# OpenSegment-v11.net
KiCad netlist of a schematic drawn in EAGLE
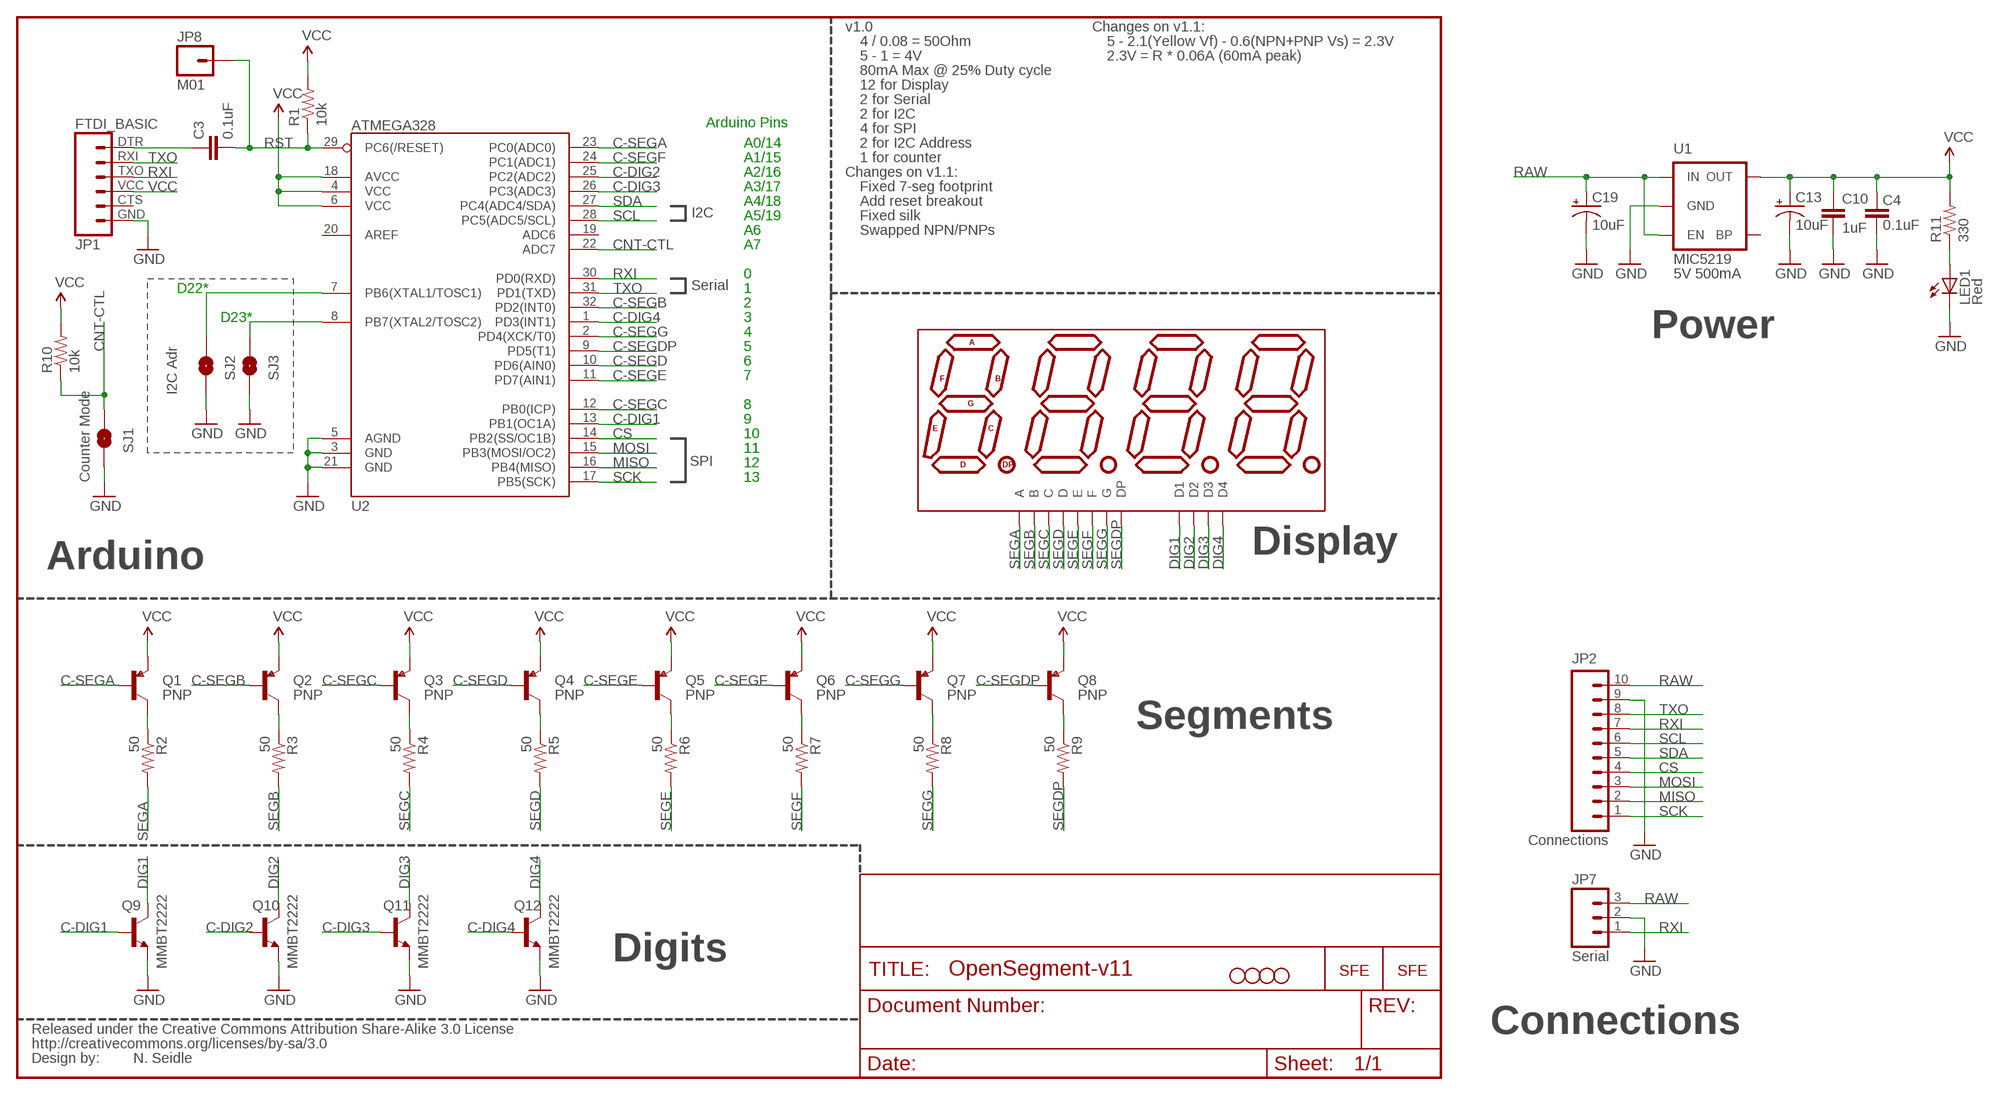
[diagram p0: schematic, sheet 1]

(export (version "E")
  (design (tool "Eeschema 10.0.6"))
  (components
    (comp (ref "C3")
      (value "0.1uF")
      (footprint "eagle-import:0402-CAP")
      (libsource (lib "eagle-import") (part "CAP0402-CAP"))
    )
    (comp (ref "C4")
      (value "0.1uF")
      (footprint "eagle-import:0402-CAP")
      (libsource (lib "eagle-import") (part "CAP0402-CAP"))
    )
    (comp (ref "C10")
      (value "1uF")
      (footprint "eagle-import:0402-CAP")
      (libsource (lib "eagle-import") (part "CAP0402-CAP"))
    )
    (comp (ref "C13")
      (value "10uF")
      (footprint "eagle-import:EIA3216")
      (libsource (lib "eagle-import") (part "CAP_POL1206"))
    )
    (comp (ref "C19")
      (value "10uF")
      (footprint "eagle-import:EIA3216")
      (libsource (lib "eagle-import") (part "CAP_POL1206"))
    )
    (comp (ref "JP1")
      (value "FTDI_BASIC")
      (footprint "eagle-import:FTDI_BASIC")
      (libsource (lib "eagle-import") (part "FTDI_BASICPTH"))
    )
    (comp (ref "JP2")
      (value "Connections")
      (footprint "eagle-import:1X10")
      (libsource (lib "eagle-import") (part "M10{dblquote}"))
    )
    (comp (ref "JP3")
      (value "STAND-OFF")
      (footprint "eagle-import:STAND-OFF")
      (libsource (lib "eagle-import") (part "STAND-OFF"))
    )
    (comp (ref "JP4")
      (value "STAND-OFF")
      (footprint "eagle-import:STAND-OFF")
      (libsource (lib "eagle-import") (part "STAND-OFF"))
    )
    (comp (ref "JP5")
      (value "STAND-OFF")
      (footprint "eagle-import:STAND-OFF")
      (libsource (lib "eagle-import") (part "STAND-OFF"))
    )
    (comp (ref "JP6")
      (value "STAND-OFF")
      (footprint "eagle-import:STAND-OFF")
      (libsource (lib "eagle-import") (part "STAND-OFF"))
    )
    (comp (ref "JP7")
      (value "Serial")
      (footprint "eagle-import:JST-3-SMD")
      (libsource (lib "eagle-import") (part "M03"))
    )
    (comp (ref "JP8")
      (value "M01")
      (footprint "eagle-import:1X01")
      (libsource (lib "eagle-import") (part "M01PTH"))
    )
    (comp (ref "LED1")
      (value "Red")
      (footprint "eagle-import:LED-0603")
      (libsource (lib "eagle-import") (part "LED0603"))
    )
    (comp (ref "Q1")
      (value "PNP")
      (footprint "eagle-import:SOT23-3")
      (libsource (lib "eagle-import") (part "TRANSISTOR_PNPSMD"))
    )
    (comp (ref "Q2")
      (value "PNP")
      (footprint "eagle-import:SOT23-3")
      (libsource (lib "eagle-import") (part "TRANSISTOR_PNPSMD"))
    )
    (comp (ref "Q3")
      (value "PNP")
      (footprint "eagle-import:SOT23-3")
      (libsource (lib "eagle-import") (part "TRANSISTOR_PNPSMD"))
    )
    (comp (ref "Q4")
      (value "PNP")
      (footprint "eagle-import:SOT23-3")
      (libsource (lib "eagle-import") (part "TRANSISTOR_PNPSMD"))
    )
    (comp (ref "Q5")
      (value "PNP")
      (footprint "eagle-import:SOT23-3")
      (libsource (lib "eagle-import") (part "TRANSISTOR_PNPSMD"))
    )
    (comp (ref "Q6")
      (value "PNP")
      (footprint "eagle-import:SOT23-3")
      (libsource (lib "eagle-import") (part "TRANSISTOR_PNPSMD"))
    )
    (comp (ref "Q7")
      (value "PNP")
      (footprint "eagle-import:SOT23-3")
      (libsource (lib "eagle-import") (part "TRANSISTOR_PNPSMD"))
    )
    (comp (ref "Q8")
      (value "PNP")
      (footprint "eagle-import:SOT23-3")
      (libsource (lib "eagle-import") (part "TRANSISTOR_PNPSMD"))
    )
    (comp (ref "Q9")
      (value "MMBT2222")
      (footprint "eagle-import:SOT23-3")
      (libsource (lib "eagle-import") (part "TRANSISTOR_NPNSOT23-3"))
    )
    (comp (ref "Q10")
      (value "MMBT2222")
      (footprint "eagle-import:SOT23-3")
      (libsource (lib "eagle-import") (part "TRANSISTOR_NPNSOT23-3"))
    )
    (comp (ref "Q11")
      (value "MMBT2222")
      (footprint "eagle-import:SOT23-3")
      (libsource (lib "eagle-import") (part "TRANSISTOR_NPNSOT23-3"))
    )
    (comp (ref "Q12")
      (value "MMBT2222")
      (footprint "eagle-import:SOT23-3")
      (libsource (lib "eagle-import") (part "TRANSISTOR_NPNSOT23-3"))
    )
    (comp (ref "R1")
      (value "10k")
      (footprint "eagle-import:0402-RES")
      (libsource (lib "eagle-import") (part "RESISTOR0402-RES"))
    )
    (comp (ref "R2")
      (value "50")
      (footprint "eagle-import:0402-RES")
      (libsource (lib "eagle-import") (part "RESISTOR0402-RES"))
    )
    (comp (ref "R3")
      (value "50")
      (footprint "eagle-import:0402-RES")
      (libsource (lib "eagle-import") (part "RESISTOR0402-RES"))
    )
    (comp (ref "R4")
      (value "50")
      (footprint "eagle-import:0402-RES")
      (libsource (lib "eagle-import") (part "RESISTOR0402-RES"))
    )
    (comp (ref "R5")
      (value "50")
      (footprint "eagle-import:0402-RES")
      (libsource (lib "eagle-import") (part "RESISTOR0402-RES"))
    )
    (comp (ref "R6")
      (value "50")
      (footprint "eagle-import:0402-RES")
      (libsource (lib "eagle-import") (part "RESISTOR0402-RES"))
    )
    (comp (ref "R7")
      (value "50")
      (footprint "eagle-import:0402-RES")
      (libsource (lib "eagle-import") (part "RESISTOR0402-RES"))
    )
    (comp (ref "R8")
      (value "50")
      (footprint "eagle-import:0402-RES")
      (libsource (lib "eagle-import") (part "RESISTOR0402-RES"))
    )
    (comp (ref "R9")
      (value "50")
      (footprint "eagle-import:0402-RES")
      (libsource (lib "eagle-import") (part "RESISTOR0402-RES"))
    )
    (comp (ref "R10")
      (value "10k")
      (footprint "eagle-import:0402-RES")
      (libsource (lib "eagle-import") (part "RESISTOR0402-RES"))
    )
    (comp (ref "R11")
      (value "330")
      (footprint "eagle-import:0402-RES")
      (libsource (lib "eagle-import") (part "RESISTOR0402-RES"))
    )
    (comp (ref "SJ1")
      (value "Counter Ctl")
      (footprint "eagle-import:SJ_2S-NO")
      (libsource (lib "eagle-import") (part "SOLDERJUMPERNO"))
    )
    (comp (ref "SJ2")
      (value "Counter Ctl")
      (footprint "eagle-import:SJ_2S-NO")
      (libsource (lib "eagle-import") (part "SOLDERJUMPERNO"))
    )
    (comp (ref "SJ3")
      (value "Counter Ctl")
      (footprint "eagle-import:SJ_2S-NO")
      (libsource (lib "eagle-import") (part "SOLDERJUMPERNO"))
    )
    (comp (ref "U$2")
      (value "LOGO-SFESK")
      (footprint "eagle-import:SFE-LOGO-FLAME")
      (libsource (lib "eagle-import") (part "LOGO-SFESK"))
    )
    (comp (ref "U$3")
      (value "CREATIVE_COMMONS")
      (footprint "eagle-import:CREATIVE_COMMONS")
      (libsource (lib "eagle-import") (part "CREATIVE_COMMONS"))
    )
    (comp (ref "U$7")
      (value "LOGO-SFENW2")
      (footprint "eagle-import:SFE-NEW-WEB")
      (libsource (lib "eagle-import") (part "LOGO-SFENW2"))
    )
    (comp (ref "U1")
      (value "MIC5219")
      (footprint "eagle-import:SOT23-5")
      (libsource (lib "eagle-import") (part "V_REG_LDOSMD"))
    )
    (comp (ref "U2")
      (value "ATMEGA328")
      (footprint "eagle-import:TQFP32-08")
      (libsource (lib "eagle-import") (part "ATMEGA168"))
    )
    (comp (ref "U3")
      (value "7-SEGMENT-4DIGIT-COUNTERPTH")
      (footprint "eagle-import:7-SEGMENT-4DIGIT-COUNTER")
      (libsource (lib "eagle-import") (part "7-SEGMENT-4DIGIT-COUNTERPTH"))
    )
  )
  (nets
    (net (code "1") (name "/C-DIG1") (class "Default")
      (node (ref "Q9") (pin "1") (pinfunction "B_1") (pintype "passive"))
      (node (ref "U2") (pin "13") (pinfunction "PB1(OC1A)_13") (pintype "bidirectional"))
    )
    (net (code "2") (name "/C-DIG2") (class "Default")
      (node (ref "Q10") (pin "1") (pinfunction "B_1") (pintype "passive"))
      (node (ref "U2") (pin "25") (pinfunction "PC2(ADC2)_25") (pintype "bidirectional"))
    )
    (net (code "3") (name "/C-DIG3") (class "Default")
      (node (ref "Q11") (pin "1") (pinfunction "B_1") (pintype "passive"))
      (node (ref "U2") (pin "26") (pinfunction "PC3(ADC3)_26") (pintype "bidirectional"))
    )
    (net (code "4") (name "/C-DIG4") (class "Default")
      (node (ref "Q12") (pin "1") (pinfunction "B_1") (pintype "passive"))
      (node (ref "U2") (pin "1") (pinfunction "PD3(INT1)_1") (pintype "bidirectional"))
    )
    (net (code "5") (name "/C-SEGA") (class "Default")
      (node (ref "Q1") (pin "1") (pinfunction "B_1") (pintype "passive"))
      (node (ref "U2") (pin "23") (pinfunction "PC0(ADC0)_23") (pintype "bidirectional"))
    )
    (net (code "6") (name "/C-SEGB") (class "Default")
      (node (ref "Q2") (pin "1") (pinfunction "B_1") (pintype "passive"))
      (node (ref "U2") (pin "32") (pinfunction "PD2(INT0)_32") (pintype "bidirectional"))
    )
    (net (code "7") (name "/C-SEGC") (class "Default")
      (node (ref "Q3") (pin "1") (pinfunction "B_1") (pintype "passive"))
      (node (ref "U2") (pin "12") (pinfunction "PB0(ICP)_12") (pintype "bidirectional"))
    )
    (net (code "8") (name "/C-SEGD") (class "Default")
      (node (ref "Q4") (pin "1") (pinfunction "B_1") (pintype "passive"))
      (node (ref "U2") (pin "10") (pinfunction "PD6(AIN0)_10") (pintype "bidirectional"))
    )
    (net (code "9") (name "/C-SEGDP") (class "Default")
      (node (ref "Q8") (pin "1") (pinfunction "B_1") (pintype "passive"))
      (node (ref "U2") (pin "9") (pinfunction "PD5(T1)_9") (pintype "bidirectional"))
    )
    (net (code "10") (name "/C-SEGE") (class "Default")
      (node (ref "Q5") (pin "1") (pinfunction "B_1") (pintype "passive"))
      (node (ref "U2") (pin "11") (pinfunction "PD7(AIN1)_11") (pintype "bidirectional"))
    )
    (net (code "11") (name "/C-SEGF") (class "Default")
      (node (ref "Q6") (pin "1") (pinfunction "B_1") (pintype "passive"))
      (node (ref "U2") (pin "24") (pinfunction "PC1(ADC1)_24") (pintype "bidirectional"))
    )
    (net (code "12") (name "/C-SEGG") (class "Default")
      (node (ref "Q7") (pin "1") (pinfunction "B_1") (pintype "passive"))
      (node (ref "U2") (pin "2") (pinfunction "PD4(XCK/T0)_2") (pintype "bidirectional"))
    )
    (net (code "13") (name "/CNT-CTL") (class "Default")
      (node (ref "R10") (pin "1") (pinfunction "1_1") (pintype "passive"))
      (node (ref "SJ1") (pin "1") (pinfunction "1_1") (pintype "passive"))
      (node (ref "U2") (pin "22") (pinfunction "ADC7_22") (pintype "bidirectional"))
    )
    (net (code "14") (name "/CS") (class "Default")
      (node (ref "JP2") (pin "4") (pinfunction "4_4") (pintype "passive"))
      (node (ref "U2") (pin "14") (pinfunction "PB2(SS/OC1B)_14") (pintype "bidirectional"))
    )
    (net (code "15") (name "/DIG1") (class "Default")
      (node (ref "Q9") (pin "3") (pinfunction "C_3") (pintype "passive"))
      (node (ref "U3") (pin "12") (pinfunction "D1_12") (pintype "bidirectional"))
    )
    (net (code "16") (name "/DIG2") (class "Default")
      (node (ref "Q10") (pin "3") (pinfunction "C_3") (pintype "passive"))
      (node (ref "U3") (pin "9") (pinfunction "D2_9") (pintype "bidirectional"))
    )
    (net (code "17") (name "/DIG3") (class "Default")
      (node (ref "Q11") (pin "3") (pinfunction "C_3") (pintype "passive"))
      (node (ref "U3") (pin "8") (pinfunction "D3_8") (pintype "bidirectional"))
    )
    (net (code "18") (name "/DIG4") (class "Default")
      (node (ref "Q12") (pin "3") (pinfunction "C_3") (pintype "passive"))
      (node (ref "U3") (pin "6") (pinfunction "D4_6") (pintype "bidirectional"))
    )
    (net (code "19") (name "/MISO") (class "Default")
      (node (ref "JP2") (pin "2") (pinfunction "2_2") (pintype "passive"))
      (node (ref "U2") (pin "16") (pinfunction "PB4(MISO)_16") (pintype "bidirectional"))
    )
    (net (code "20") (name "/MOSI") (class "Default")
      (node (ref "JP2") (pin "3") (pinfunction "3_3") (pintype "passive"))
      (node (ref "U2") (pin "15") (pinfunction "PB3(MOSI/OC2)_15") (pintype "bidirectional"))
    )
    (net (code "21") (name "/RAW") (class "Default")
      (node (ref "C19") (pin "A") (pinfunction "+_A") (pintype "passive"))
      (node (ref "JP2") (pin "10") (pinfunction "10_10") (pintype "passive"))
      (node (ref "JP7") (pin "3") (pinfunction "3_3") (pintype "passive"))
      (node (ref "U1") (pin "1") (pinfunction "IN_1") (pintype "input"))
      (node (ref "U1") (pin "3") (pinfunction "EN_3") (pintype "input"))
    )
    (net (code "22") (name "/RST") (class "Default")
      (node (ref "C3") (pin "2") (pinfunction "2_2") (pintype "passive"))
      (node (ref "JP8") (pin "1") (pinfunction "1_1") (pintype "passive"))
      (node (ref "R1") (pin "1") (pinfunction "1_1") (pintype "passive"))
      (node (ref "U2") (pin "29") (pinfunction "PC6(/RESET)_29") (pintype "bidirectional"))
    )
    (net (code "23") (name "/RXI") (class "Default")
      (node (ref "JP1") (pin "TXO") (pinfunction "3_TXO") (pintype "passive"))
      (node (ref "JP2") (pin "7") (pinfunction "7_7") (pintype "passive"))
      (node (ref "JP7") (pin "1") (pinfunction "1_1") (pintype "passive"))
      (node (ref "U2") (pin "30") (pinfunction "PD0(RXD)_30") (pintype "bidirectional"))
    )
    (net (code "24") (name "/SCK") (class "Default")
      (node (ref "JP2") (pin "1") (pinfunction "1_1") (pintype "passive"))
      (node (ref "U2") (pin "17") (pinfunction "PB5(SCK)_17") (pintype "bidirectional"))
    )
    (net (code "25") (name "/SCL") (class "Default")
      (node (ref "JP2") (pin "6") (pinfunction "6_6") (pintype "passive"))
      (node (ref "U2") (pin "28") (pinfunction "PC5(ADC5/SCL)_28") (pintype "bidirectional"))
    )
    (net (code "26") (name "/SDA") (class "Default")
      (node (ref "JP2") (pin "5") (pinfunction "5_5") (pintype "passive"))
      (node (ref "U2") (pin "27") (pinfunction "PC4(ADC4/SDA)_27") (pintype "bidirectional"))
    )
    (net (code "27") (name "/SEGA") (class "Default")
      (node (ref "R2") (pin "2") (pinfunction "2_2") (pintype "passive"))
      (node (ref "U3") (pin "11") (pinfunction "A_11") (pintype "bidirectional"))
    )
    (net (code "28") (name "/SEGB") (class "Default")
      (node (ref "R3") (pin "2") (pinfunction "2_2") (pintype "passive"))
      (node (ref "U3") (pin "7") (pinfunction "B_7") (pintype "bidirectional"))
    )
    (net (code "29") (name "/SEGC") (class "Default")
      (node (ref "R4") (pin "2") (pinfunction "2_2") (pintype "passive"))
      (node (ref "U3") (pin "4") (pinfunction "C_4") (pintype "bidirectional"))
    )
    (net (code "30") (name "/SEGD") (class "Default")
      (node (ref "R5") (pin "2") (pinfunction "2_2") (pintype "passive"))
      (node (ref "U3") (pin "2") (pinfunction "D_2") (pintype "bidirectional"))
    )
    (net (code "31") (name "/SEGDP") (class "Default")
      (node (ref "R9") (pin "2") (pinfunction "2_2") (pintype "passive"))
      (node (ref "U3") (pin "3") (pinfunction "DP_3") (pintype "bidirectional"))
    )
    (net (code "32") (name "/SEGE") (class "Default")
      (node (ref "R6") (pin "2") (pinfunction "2_2") (pintype "passive"))
      (node (ref "U3") (pin "1") (pinfunction "E_1") (pintype "bidirectional"))
    )
    (net (code "33") (name "/SEGF") (class "Default")
      (node (ref "R7") (pin "2") (pinfunction "2_2") (pintype "passive"))
      (node (ref "U3") (pin "10") (pinfunction "F_10") (pintype "bidirectional"))
    )
    (net (code "34") (name "/SEGG") (class "Default")
      (node (ref "R8") (pin "2") (pinfunction "2_2") (pintype "passive"))
      (node (ref "U3") (pin "5") (pinfunction "G_5") (pintype "bidirectional"))
    )
    (net (code "35") (name "/TXO") (class "Default")
      (node (ref "JP1") (pin "RXI") (pinfunction "2_RXI") (pintype "passive"))
      (node (ref "JP2") (pin "8") (pinfunction "8_8") (pintype "passive"))
      (node (ref "U2") (pin "31") (pinfunction "PD1(TXD)_31") (pintype "bidirectional"))
    )
    (net (code "36") (name "GND") (class "Default")
      (node (ref "C10") (pin "2") (pinfunction "2_2") (pintype "passive"))
      (node (ref "C13") (pin "C") (pinfunction "-_C") (pintype "passive"))
      (node (ref "C19") (pin "C") (pinfunction "-_C") (pintype "passive"))
      (node (ref "C4") (pin "1") (pinfunction "1_1") (pintype "passive"))
      (node (ref "JP1") (pin "GND") (pinfunction "6_GND") (pintype "passive"))
      (node (ref "JP2") (pin "9") (pinfunction "9_9") (pintype "passive"))
      (node (ref "JP7") (pin "2") (pinfunction "2_2") (pintype "passive"))
      (node (ref "LED1") (pin "C") (pinfunction "C_C") (pintype "passive"))
      (node (ref "Q10") (pin "2") (pinfunction "E_2") (pintype "passive"))
      (node (ref "Q11") (pin "2") (pinfunction "E_2") (pintype "passive"))
      (node (ref "Q12") (pin "2") (pinfunction "E_2") (pintype "passive"))
      (node (ref "Q9") (pin "2") (pinfunction "E_2") (pintype "passive"))
      (node (ref "SJ1") (pin "2") (pinfunction "2_2") (pintype "passive"))
      (node (ref "SJ2") (pin "2") (pinfunction "2_2") (pintype "passive"))
      (node (ref "SJ3") (pin "2") (pinfunction "2_2") (pintype "passive"))
      (node (ref "U1") (pin "2") (pinfunction "GND_2") (pintype "input"))
      (node (ref "U2") (pin "21") (pinfunction "GND_21") (pintype "bidirectional"))
      (node (ref "U2") (pin "3") (pinfunction "GND_3") (pintype "bidirectional"))
      (node (ref "U2") (pin "5") (pinfunction "AGND_5") (pintype "bidirectional"))
    )
    (net (code "37") (name "Net-(JP1-1)") (class "Default")
      (node (ref "C3") (pin "1") (pinfunction "1_1") (pintype "passive"))
      (node (ref "JP1") (pin "DTR") (pinfunction "1_DTR") (pintype "passive"))
    )
    (net (code "38") (name "Net-(LED1-PadA)") (class "Default")
      (node (ref "LED1") (pin "A") (pinfunction "A_A") (pintype "passive"))
      (node (ref "R11") (pin "1") (pinfunction "1_1") (pintype "passive"))
    )
    (net (code "39") (name "Net-(Q1-C)") (class "Default")
      (node (ref "Q1") (pin "3") (pinfunction "C_3") (pintype "passive"))
      (node (ref "R2") (pin "1") (pinfunction "1_1") (pintype "passive"))
    )
    (net (code "40") (name "Net-(Q2-C)") (class "Default")
      (node (ref "Q2") (pin "3") (pinfunction "C_3") (pintype "passive"))
      (node (ref "R3") (pin "1") (pinfunction "1_1") (pintype "passive"))
    )
    (net (code "41") (name "Net-(Q3-C)") (class "Default")
      (node (ref "Q3") (pin "3") (pinfunction "C_3") (pintype "passive"))
      (node (ref "R4") (pin "1") (pinfunction "1_1") (pintype "passive"))
    )
    (net (code "42") (name "Net-(Q4-C)") (class "Default")
      (node (ref "Q4") (pin "3") (pinfunction "C_3") (pintype "passive"))
      (node (ref "R5") (pin "1") (pinfunction "1_1") (pintype "passive"))
    )
    (net (code "43") (name "Net-(Q5-C)") (class "Default")
      (node (ref "Q5") (pin "3") (pinfunction "C_3") (pintype "passive"))
      (node (ref "R6") (pin "1") (pinfunction "1_1") (pintype "passive"))
    )
    (net (code "44") (name "Net-(Q6-C)") (class "Default")
      (node (ref "Q6") (pin "3") (pinfunction "C_3") (pintype "passive"))
      (node (ref "R7") (pin "1") (pinfunction "1_1") (pintype "passive"))
    )
    (net (code "45") (name "Net-(Q7-C)") (class "Default")
      (node (ref "Q7") (pin "3") (pinfunction "C_3") (pintype "passive"))
      (node (ref "R8") (pin "1") (pinfunction "1_1") (pintype "passive"))
    )
    (net (code "46") (name "Net-(Q8-C)") (class "Default")
      (node (ref "Q8") (pin "3") (pinfunction "C_3") (pintype "passive"))
      (node (ref "R9") (pin "1") (pinfunction "1_1") (pintype "passive"))
    )
    (net (code "47") (name "Net-(U2-PB6(XTAL1{slash}TOSC1))") (class "Default")
      (node (ref "SJ2") (pin "1") (pinfunction "1_1") (pintype "passive"))
      (node (ref "U2") (pin "7") (pinfunction "PB6(XTAL1/TOSC1)_7") (pintype "bidirectional"))
    )
    (net (code "48") (name "Net-(U2-PB7(XTAL2{slash}TOSC2))") (class "Default")
      (node (ref "SJ3") (pin "1") (pinfunction "1_1") (pintype "passive"))
      (node (ref "U2") (pin "8") (pinfunction "PB7(XTAL2/TOSC2)_8") (pintype "bidirectional"))
    )
    (net (code "49") (name "VCC") (class "Default")
      (node (ref "C10") (pin "1") (pinfunction "1_1") (pintype "passive"))
      (node (ref "C13") (pin "A") (pinfunction "+_A") (pintype "passive"))
      (node (ref "C4") (pin "2") (pinfunction "2_2") (pintype "passive"))
      (node (ref "JP1") (pin "VCC") (pinfunction "4_VCC") (pintype "passive"))
      (node (ref "Q1") (pin "2") (pinfunction "E_2") (pintype "passive"))
      (node (ref "Q2") (pin "2") (pinfunction "E_2") (pintype "passive"))
      (node (ref "Q3") (pin "2") (pinfunction "E_2") (pintype "passive"))
      (node (ref "Q4") (pin "2") (pinfunction "E_2") (pintype "passive"))
      (node (ref "Q5") (pin "2") (pinfunction "E_2") (pintype "passive"))
      (node (ref "Q6") (pin "2") (pinfunction "E_2") (pintype "passive"))
      (node (ref "Q7") (pin "2") (pinfunction "E_2") (pintype "passive"))
      (node (ref "Q8") (pin "2") (pinfunction "E_2") (pintype "passive"))
      (node (ref "R1") (pin "2") (pinfunction "2_2") (pintype "passive"))
      (node (ref "R10") (pin "2") (pinfunction "2_2") (pintype "passive"))
      (node (ref "R11") (pin "2") (pinfunction "2_2") (pintype "passive"))
      (node (ref "U1") (pin "5") (pinfunction "OUT_5") (pintype "passive"))
      (node (ref "U2") (pin "18") (pinfunction "AVCC_18") (pintype "bidirectional"))
      (node (ref "U2") (pin "4") (pinfunction "VCC_4") (pintype "bidirectional"))
      (node (ref "U2") (pin "6") (pinfunction "VCC_6") (pintype "bidirectional"))
    )
    (net (code "50") (name "unconnected-(JP1-5-PadCTS)") (class "Default")
      (node (ref "JP1") (pin "CTS") (pinfunction "5_CTS") (pintype "passive"))
    )
    (net (code "51") (name "unconnected-(U1-BP-Pad4)") (class "Default")
      (node (ref "U1") (pin "4") (pinfunction "BP_4") (pintype "input"))
    )
    (net (code "52") (name "unconnected-(U2-ADC6-Pad19)") (class "Default")
      (node (ref "U2") (pin "19") (pinfunction "ADC6_19") (pintype "bidirectional"))
    )
    (net (code "53") (name "unconnected-(U2-AREF-Pad20)") (class "Default")
      (node (ref "U2") (pin "20") (pinfunction "AREF_20") (pintype "bidirectional"))
    )
  )
)
